# ntpi_adapter_v1_led.net
KiCad netlist of a schematic drawn in EAGLE
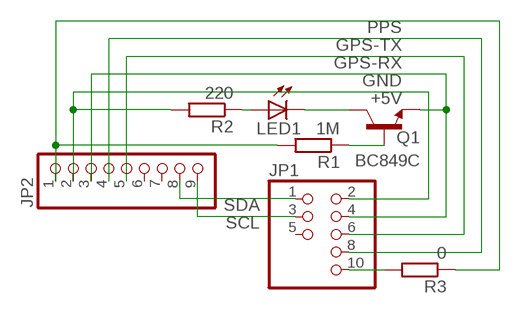
[diagram p0: schematic, sheet 1]

(export (version "E")
  (design (tool "Eeschema 10.0.6"))
  (components
    (comp (ref "JP1")
      (value "PINHEAD-NTPI")
      (footprint "eagle-import:PINHEAD-NTPI")
      (libsource (lib "eagle-import") (part "PINHEAD-NTPI"))
    )
    (comp (ref "JP2")
      (value "PINHD-1X9")
      (footprint "eagle-import:1X09")
      (libsource (lib "eagle-import") (part "PINHD-1X9"))
    )
    (comp (ref "LED1")
      (value "LEDCHIPLED_0805")
      (footprint "eagle-import:CHIPLED_0805")
      (libsource (lib "eagle-import") (part "LEDCHIPLED_0805"))
    )
    (comp (ref "Q1")
      (value "BC849C")
      (footprint "eagle-import:SOT23")
      (libsource (lib "eagle-import") (part "BC848SMDA"))
    )
    (comp (ref "R1")
      (value "1M")
      (footprint "eagle-import:R0805W")
      (libsource (lib "eagle-import") (part "R-EU_R0805W"))
    )
    (comp (ref "R2")
      (value "220")
      (footprint "eagle-import:R0805W")
      (libsource (lib "eagle-import") (part "R-EU_R0805W"))
    )
    (comp (ref "R3")
      (value "0")
      (footprint "eagle-import:R0805W")
      (libsource (lib "eagle-import") (part "R-EU_R0805W"))
    )
  )
  (nets
    (net (code "1") (name "/+5V") (class "Default")
      (node (ref "JP1") (pin "2") (pinfunction "2_2") (pintype "passive"))
      (node (ref "JP2") (pin "2") (pinfunction "2_2") (pintype "passive"))
      (node (ref "R2") (pin "2") (pinfunction "2_2") (pintype "passive"))
    )
    (net (code "2") (name "/GND") (class "Default")
      (node (ref "JP1") (pin "4") (pinfunction "4_4") (pintype "passive"))
      (node (ref "JP2") (pin "3") (pinfunction "3_3") (pintype "passive"))
      (node (ref "Q1") (pin "2") (pinfunction "E_2") (pintype "passive"))
    )
    (net (code "3") (name "/GPS-RX") (class "Default")
      (node (ref "JP1") (pin "6") (pinfunction "6_6") (pintype "passive"))
      (node (ref "JP2") (pin "5") (pinfunction "5_5") (pintype "passive"))
    )
    (net (code "4") (name "/GPS-TX") (class "Default")
      (node (ref "JP1") (pin "8") (pinfunction "8_8") (pintype "passive"))
      (node (ref "JP2") (pin "4") (pinfunction "4_4") (pintype "passive"))
    )
    (net (code "5") (name "/PPS") (class "Default")
      (node (ref "JP2") (pin "1") (pinfunction "1_1") (pintype "passive"))
      (node (ref "R1") (pin "2") (pinfunction "2_2") (pintype "passive"))
      (node (ref "R3") (pin "1") (pinfunction "1_1") (pintype "passive"))
    )
    (net (code "6") (name "/SCL") (class "Default")
      (node (ref "JP1") (pin "3") (pinfunction "3_3") (pintype "passive"))
      (node (ref "JP2") (pin "9") (pinfunction "9_9") (pintype "passive"))
    )
    (net (code "7") (name "/SDA") (class "Default")
      (node (ref "JP1") (pin "1") (pinfunction "1_1") (pintype "passive"))
      (node (ref "JP2") (pin "8") (pinfunction "8_8") (pintype "passive"))
    )
    (net (code "8") (name "Net-(JP1-Pad10)") (class "Default")
      (node (ref "JP1") (pin "10") (pinfunction "10_10") (pintype "passive"))
      (node (ref "R3") (pin "2") (pinfunction "2_2") (pintype "passive"))
    )
    (net (code "9") (name "Net-(LED1-PadA)") (class "Default")
      (node (ref "LED1") (pin "A") (pinfunction "A_A") (pintype "passive"))
      (node (ref "R2") (pin "1") (pinfunction "1_1") (pintype "passive"))
    )
    (net (code "10") (name "Net-(Q1-B)") (class "Default")
      (node (ref "Q1") (pin "1") (pinfunction "B_1") (pintype "passive"))
      (node (ref "R1") (pin "1") (pinfunction "1_1") (pintype "passive"))
    )
    (net (code "11") (name "Net-(Q1-C)") (class "Default")
      (node (ref "LED1") (pin "C") (pinfunction "C_C") (pintype "passive"))
      (node (ref "Q1") (pin "3") (pinfunction "C_3") (pintype "passive"))
    )
    (net (code "12") (name "unconnected-(JP1-Pad5)") (class "Default")
      (node (ref "JP1") (pin "5") (pinfunction "5_5") (pintype "passive"))
    )
    (net (code "13") (name "unconnected-(JP2-Pad6)") (class "Default")
      (node (ref "JP2") (pin "6") (pinfunction "6_6") (pintype "passive"))
    )
    (net (code "14") (name "unconnected-(JP2-Pad7)") (class "Default")
      (node (ref "JP2") (pin "7") (pinfunction "7_7") (pintype "passive"))
    )
  )
)
